# Power_Supply.net
KiCad netlist of a schematic drawn in Altium Designer
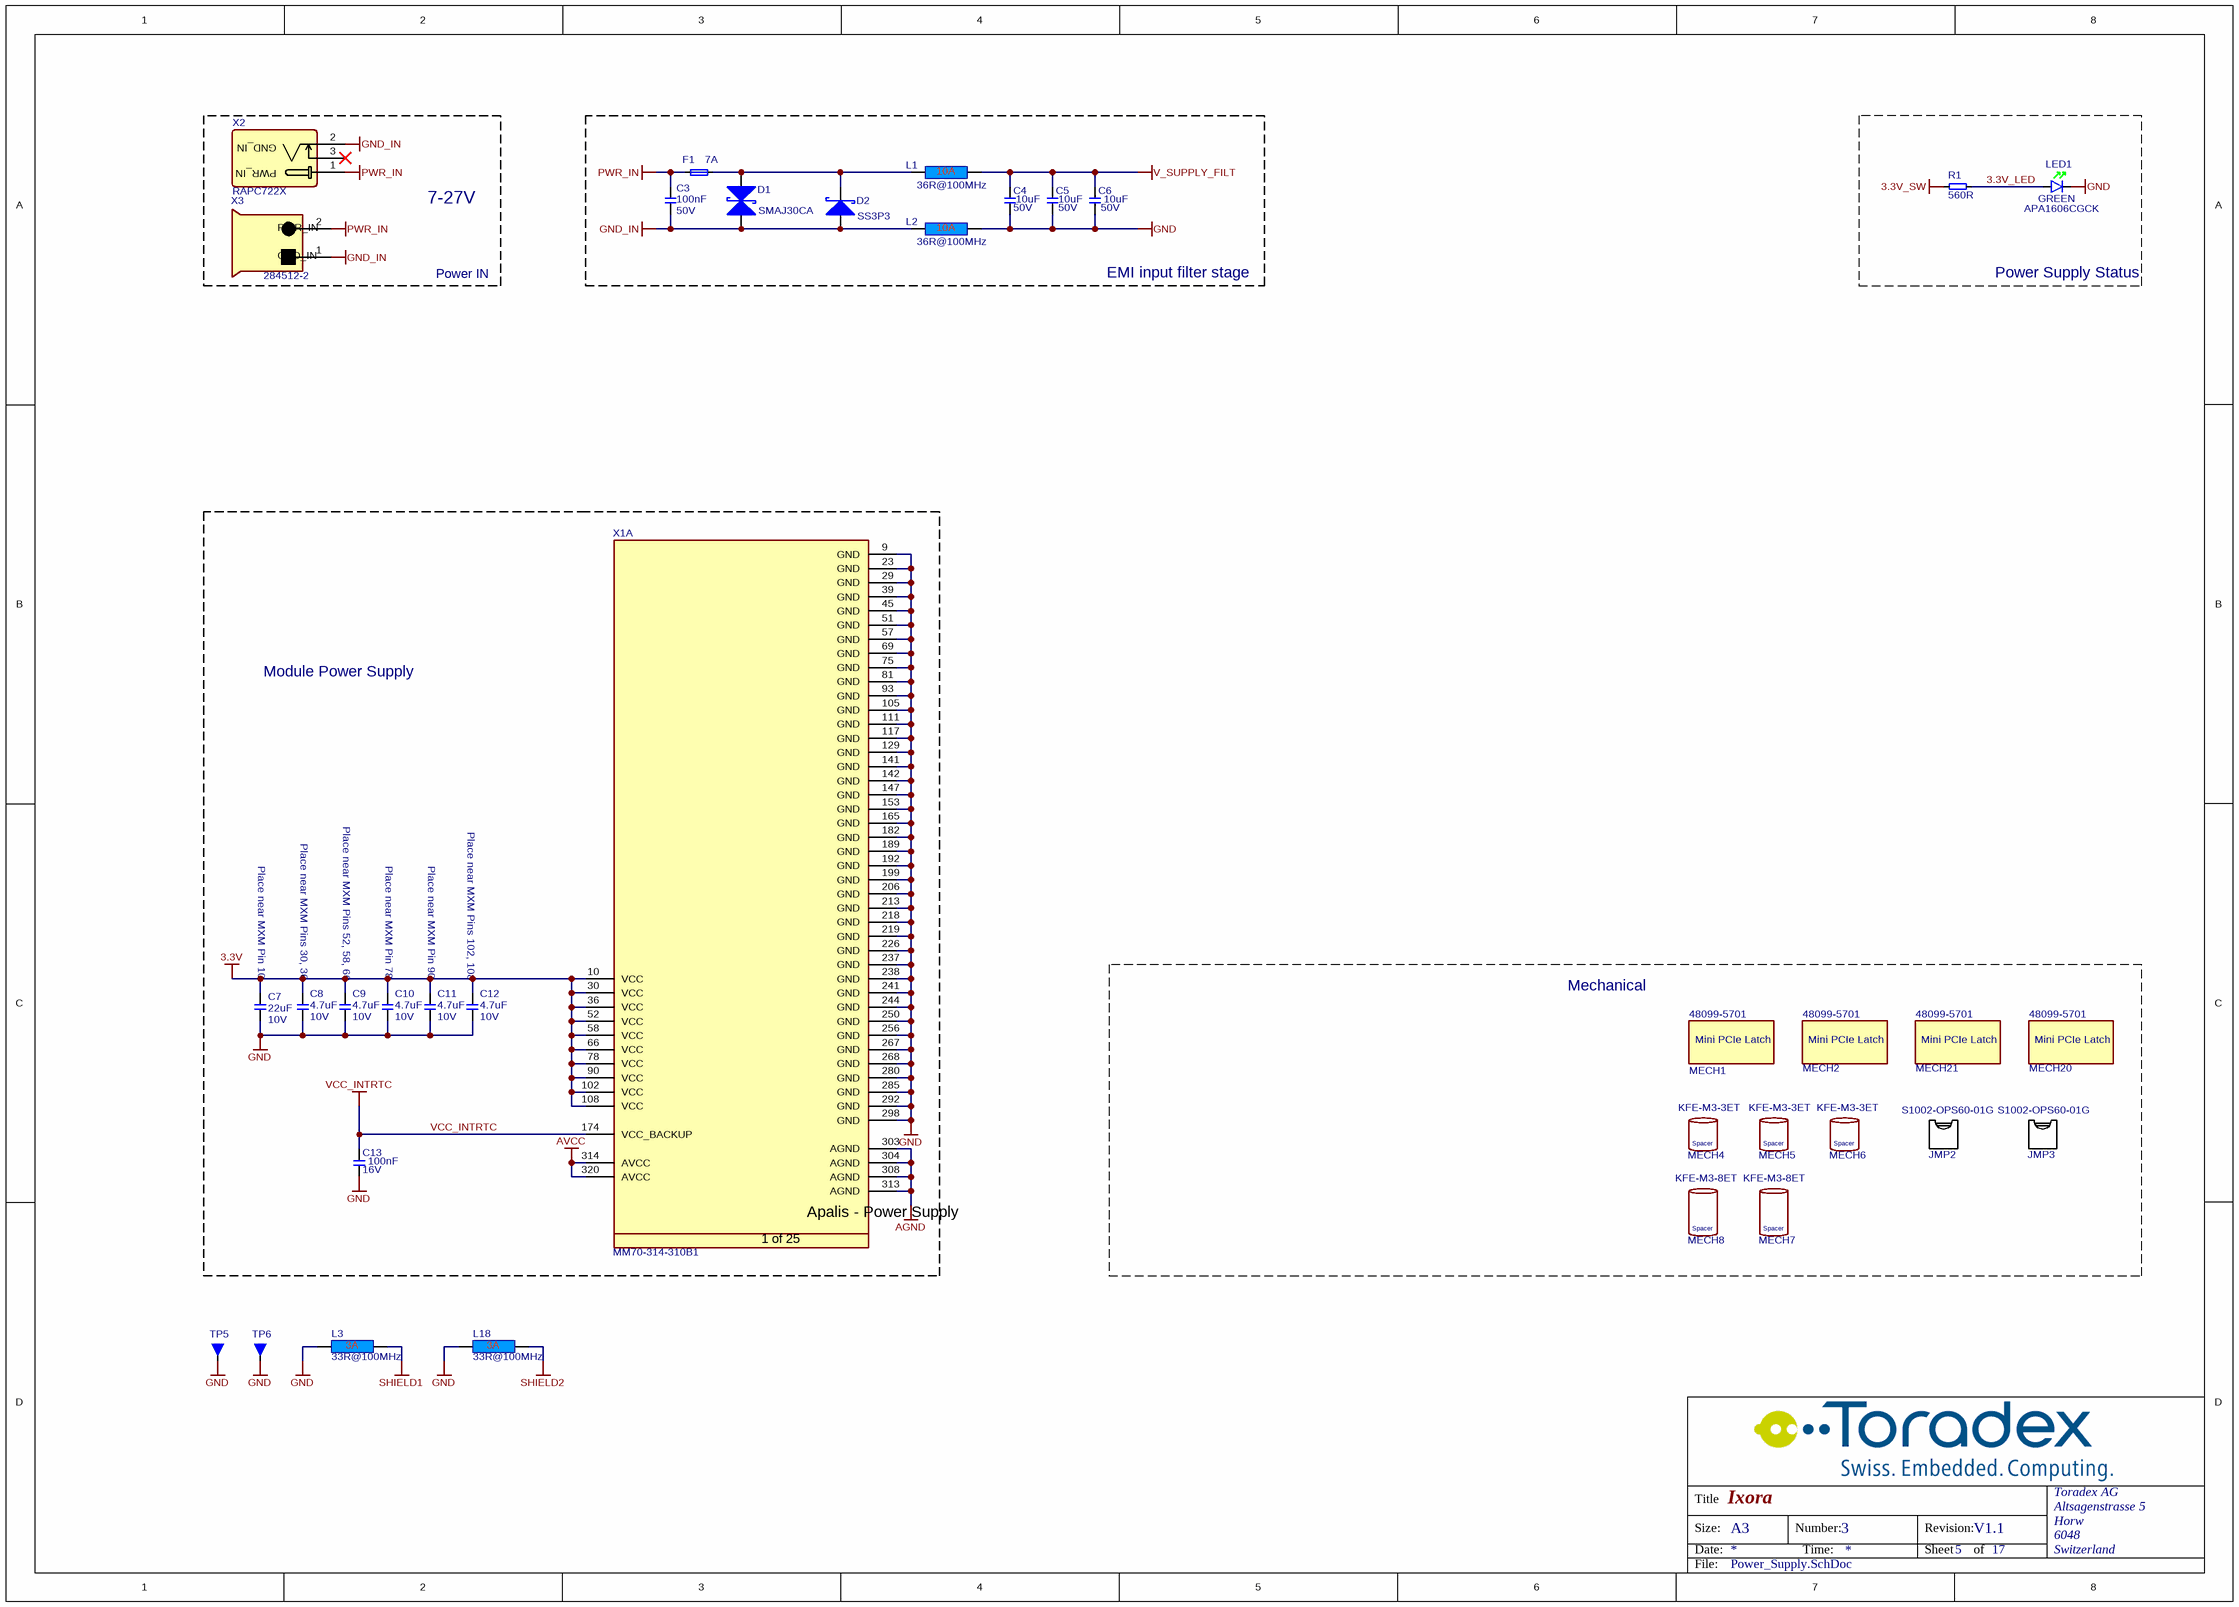
[diagram p0: Power_Supply.SchDoc]

(export (version "E")
  (design (tool "Eeschema 10.0.6"))
  (components
    (comp (ref "C3")
      (value "100nF")
      (footprint "T_CAPC0603X33N")
      (description "Capacitor Ceramic X7R 100nF 50V 20% 0603")
      (fields (field (name "TOLERANCE") "20%") (field (name "RATING") "50V"))
      (libsource (lib "Ixora") (part "C-X7R-100nF-50V-20%-0603"))
    )
    (comp (ref "C4")
      (value "10uF")
      (footprint "CAPC3225X160N")
      (description "Capacitor Ceramic X5R 10uF 50V 20% 1210")
      (fields (field (name "TOLERANCE") "20%") (field (name "RATING") "50V"))
      (libsource (lib "Ixora") (part "C-X5R-10uF-50V-20%-1210"))
    )
    (comp (ref "C5")
      (value "10uF")
      (footprint "CAPC3225X160N")
      (description "Capacitor Ceramic X5R 10uF 50V 20% 1210")
      (fields (field (name "TOLERANCE") "20%") (field (name "RATING") "50V"))
      (libsource (lib "Ixora") (part "C-X5R-10uF-50V-20%-1210"))
    )
    (comp (ref "C6")
      (value "10uF")
      (footprint "CAPC3225X160N")
      (description "Capacitor Ceramic X5R 10uF 50V 20% 1210")
      (fields (field (name "TOLERANCE") "20%") (field (name "RATING") "50V"))
      (libsource (lib "Ixora") (part "C-X5R-10uF-50V-20%-1210"))
    )
    (comp (ref "C7")
      (value "22uF")
      (footprint "T_CAPC0805X125N")
      (description "Capacitor Ceramic X5R 22uF 10V 20% 0805")
      (fields (field (name "TOLERANCE") "20%") (field (name "RATING") "10V"))
      (libsource (lib "Ixora") (part "C-X5R-22uF-10V-20%-0805"))
    )
    (comp (ref "C8")
      (value "4.7uF")
      (footprint "T_CAPC0603X33N")
      (description "Capacitor Ceramic X5R 4.7uF 10V 10% 0603")
      (fields (field (name "TOLERANCE") "10%") (field (name "RATING") "10V"))
      (libsource (lib "Ixora") (part "C-X5R-4.7uF-10V-10%-0603"))
    )
    (comp (ref "C9")
      (value "4.7uF")
      (footprint "T_CAPC0603X33N")
      (description "Capacitor Ceramic X5R 4.7uF 10V 10% 0603")
      (fields (field (name "TOLERANCE") "10%") (field (name "RATING") "10V"))
      (libsource (lib "Ixora") (part "C-X5R-4.7uF-10V-10%-0603"))
    )
    (comp (ref "C10")
      (value "4.7uF")
      (footprint "T_CAPC0603X33N")
      (description "Capacitor Ceramic X5R 4.7uF 10V 10% 0603")
      (fields (field (name "TOLERANCE") "10%") (field (name "RATING") "10V"))
      (libsource (lib "Ixora") (part "C-X5R-4.7uF-10V-10%-0603"))
    )
    (comp (ref "C11")
      (value "4.7uF")
      (footprint "T_CAPC0603X33N")
      (description "Capacitor Ceramic X5R 4.7uF 10V 10% 0603")
      (fields (field (name "TOLERANCE") "10%") (field (name "RATING") "10V"))
      (libsource (lib "Ixora") (part "C-X5R-4.7uF-10V-10%-0603"))
    )
    (comp (ref "C12")
      (value "4.7uF")
      (footprint "T_CAPC0603X33N")
      (description "Capacitor Ceramic X5R 4.7uF 10V 10% 0603")
      (fields (field (name "TOLERANCE") "10%") (field (name "RATING") "10V"))
      (libsource (lib "Ixora") (part "C-X5R-4.7uF-10V-10%-0603"))
    )
    (comp (ref "C13")
      (value "100nF")
      (footprint "CAPC1005X60N")
      (description "Capacitor Ceramic X7R 100nF 16V 10% 0402")
      (fields (field (name "TOLERANCE") "10%") (field (name "RATING") "16V"))
      (libsource (lib "Ixora") (part "C-X7R-100nF-16V-10%-0402"))
    )
    (comp (ref "D1")
      (value "D-Littelfuse-SMAJ30CA-Schottky")
      (footprint "T_LITTLEFUSE_SMAJ30CA")
      (description "Bidirectional ESD protection")
      (fields (field (name "MANUFACTURER PART NO.") "SMAJ30CA"))
      (libsource (lib "Ixora") (part "D-Littelfuse-SMAJ30CA-Schottky"))
    )
    (comp (ref "D2")
      (value "SS3P3")
      (footprint "T_VISHAY_SS3P3")
      (description "SS3P3-E3/84A Schottky Diode")
      (fields (field (name "MANUFACTURER PART NO.") "SS3P3-E3/84A"))
      (libsource (lib "Ixora") (part "D-Vishay-SS3P3-E3/84A-Schottky"))
    )
    (comp (ref "F1")
      (value "7A")
      (footprint "T_Littelfuse_0458")
      (description "Fuse 7A Fast")
      (fields (field (name "MANUFACTURER PART NO.") "0458007"))
      (libsource (lib "Ixora") (part "F-Littelfuse-0458007"))
    )
    (comp (ref "JMP2")
      (value "Shunt Jumper")
      (fields (field (name "MANUFACTURER PART NO.") "S1002-OPS60-01G"))
      (libsource (lib "Ixora") (part "MECH-Shunt-Jumper-Black-2.54mm"))
    )
    (comp (ref "JMP3")
      (value "Shunt Jumper")
      (fields (field (name "MANUFACTURER PART NO.") "S1002-OPS60-01G"))
      (libsource (lib "Ixora") (part "MECH-Shunt-Jumper-Black-2.54mm"))
    )
    (comp (ref "L1")
      (value "36R@100MHz")
      (footprint "T_Laird_35F0121-0SR-10")
      (description "Power Supply FB 10A")
      (fields (field (name "TOLERANCE") "25%"))
      (libsource (lib "Ixora") (part "L-Laird-35F0121-0SR-10-10A-25%"))
    )
    (comp (ref "L2")
      (value "36R@100MHz")
      (footprint "T_Laird_35F0121-0SR-10")
      (description "Power Supply FB 10A")
      (fields (field (name "TOLERANCE") "25%"))
      (libsource (lib "Ixora") (part "L-Laird-35F0121-0SR-10-10A-25%"))
    )
    (comp (ref "L3")
      (value "33R@100MHz")
      (footprint "INDC1608X95N")
      (description "33R@100MHz 3A EMI FILTER")
      (fields (field (name "TOLERANCE") "25%"))
      (libsource (lib "Ixora") (part "L-33R@100MHz-3A-25%-0603"))
    )
    (comp (ref "L18")
      (value "33R@100MHz")
      (footprint "INDC1608X95N")
      (description "33R@100MHz 3A EMI FILTER")
      (fields (field (name "TOLERANCE") "25%"))
      (libsource (lib "Ixora") (part "L-33R@100MHz-3A-25%-0603"))
    )
    (comp (ref "LED1")
      (value "APA1606CGCK")
      (footprint "T_Kingbright_APA1606CGCK")
      (description "LED green Kingbright APA1606CGCK")
      (fields (field (name "COLOR") "GREEN") (field (name "MANUFACTURER PART NO.") "APA1606CGCK"))
      (libsource (lib "Ixora") (part "LED-Kingbright-APA1606CGCK"))
    )
    (comp (ref "MECH1")
      (value "MECH-Mini-PCIe Latch")
      (footprint "T_Molex_48099-5701")
      (description "Mini-PCIe Latch")
      (fields (field (name "MANUFACTURER PART NO.") "48099-5701"))
      (libsource (lib "Ixora") (part "MECH-Molex-48099-5701"))
    )
    (comp (ref "MECH2")
      (value "MECH-Mini-PCIe Latch")
      (footprint "T_Molex_48099-5701")
      (description "Mini-PCIe Latch")
      (fields (field (name "MANUFACTURER PART NO.") "48099-5701"))
      (libsource (lib "Ixora") (part "MECH-Molex-48099-5701"))
    )
    (comp (ref "MECH4")
      (value "KFE-M3-3ET")
      (description "Spacer 3mm M3")
      (fields (field (name "MANUFACTURER PART NO.") "KFE-M3-3ET"))
      (libsource (lib "Ixora") (part "MECH-HiTech-KFE-M3-3ET"))
    )
    (comp (ref "MECH5")
      (value "KFE-M3-3ET")
      (description "Spacer 3mm M3")
      (fields (field (name "MANUFACTURER PART NO.") "KFE-M3-3ET"))
      (libsource (lib "Ixora") (part "MECH-HiTech-KFE-M3-3ET"))
    )
    (comp (ref "MECH6")
      (value "KFE-M3-3ET")
      (description "Spacer 3mm M3")
      (fields (field (name "MANUFACTURER PART NO.") "KFE-M3-3ET"))
      (libsource (lib "Ixora") (part "MECH-HiTech-KFE-M3-3ET"))
    )
    (comp (ref "MECH7")
      (value "KFE-M3-8ET")
      (description "Spacer 8mm M3")
      (fields (field (name "MANUFACTURER PART NO.") "KFE-M3-8ET"))
      (libsource (lib "Ixora") (part "MECH-HiTech-KFE-M3-8ET"))
    )
    (comp (ref "MECH8")
      (value "KFE-M3-8ET")
      (description "Spacer 8mm M3")
      (fields (field (name "MANUFACTURER PART NO.") "KFE-M3-8ET"))
      (libsource (lib "Ixora") (part "MECH-HiTech-KFE-M3-8ET"))
    )
    (comp (ref "MECH20")
      (value "MECH-Mini-PCIe Latch")
      (description "Mini-PCIe Latch")
      (fields (field (name "MANUFACTURER PART NO.") "48099-5701"))
      (libsource (lib "Ixora") (part "MECH-Molex-48099-5701"))
    )
    (comp (ref "MECH21")
      (value "MECH-Mini-PCIe Latch")
      (description "Mini-PCIe Latch")
      (fields (field (name "MANUFACTURER PART NO.") "48099-5701"))
      (libsource (lib "Ixora") (part "MECH-Molex-48099-5701"))
    )
    (comp (ref "R1")
      (value "560R")
      (footprint "RESC1005X40N")
      (description "Resistor 560 ohm 63mW 5% 0402")
      (fields (field (name "TOLERANCE") "5%"))
      (libsource (lib "Ixora") (part "R-560R-63mW-5%-0402"))
    )
    (comp (ref "TP5")
      (value "5011")
      (footprint "T_TP-THT - EYE")
      (description "Testpin Eye TH")
      (libsource (lib "Ixora") (part "TP-Keystone-5011"))
    )
    (comp (ref "TP6")
      (value "5011")
      (footprint "T_TP-THT - EYE")
      (description "Testpin Eye TH")
      (libsource (lib "Ixora") (part "TP-Keystone-5011"))
    )
    (comp (ref "X1")
      (value "CON-JAE-MM70-314-310B1-314-0.5mm")
      (footprint "T_JAE_MM70-314-310B1")
      (description "MXM3 Connector")
      (fields (field (name "MANUFACTURER PART NO.") "MM70-314-310B1"))
      (libsource (lib "Ixora") (part "CON-JAE-MM70-314-310B1-314-0.5mm"))
    )
    (comp (ref "X2")
      (value "RAPC722X")
      (footprint "T_RAPC722X")
      (description "Power Jack")
      (fields (field (name "MANUFACTURER PART NO.") "RAPC722X"))
      (libsource (lib "Ixora") (part "CON-SWC-RAPC722X"))
    )
    (comp (ref "X3")
      (value "284512-2")
      (footprint "T_TYCO_284512-2")
      (description "Power Connector")
      (fields (field (name "MANUFACTURER PART NO.") "284512-2"))
      (libsource (lib "Ixora") (part "CON-Tyco-284512-2-1x2-3.5mm"))
    )
  )
  (nets
    (net (code "1") (name "/3.3V_LED") (class "Default")
      (node (ref "LED1") (pin "2") (pinfunction "A_2") (pintype "passive"))
      (node (ref "R1") (pin "2") (pinfunction "2_2") (pintype "passive"))
    )
    (net (code "2") (name "3.3V") (class "Default")
      (node (ref "C10") (pin "1") (pinfunction "1_1") (pintype "passive"))
      (node (ref "C11") (pin "1") (pinfunction "1_1") (pintype "passive"))
      (node (ref "C12") (pin "1") (pinfunction "1_1") (pintype "passive"))
      (node (ref "C7") (pin "1") (pinfunction "1_1") (pintype "passive"))
      (node (ref "C8") (pin "1") (pinfunction "1_1") (pintype "passive"))
      (node (ref "C9") (pin "1") (pinfunction "1_1") (pintype "passive"))
      (node (ref "X1") (pin "10") (pinfunction "VCC_10") (pintype "passive"))
      (node (ref "X1") (pin "102") (pinfunction "VCC_102") (pintype "passive"))
      (node (ref "X1") (pin "108") (pinfunction "VCC_108") (pintype "passive"))
      (node (ref "X1") (pin "30") (pinfunction "VCC_30") (pintype "passive"))
      (node (ref "X1") (pin "36") (pinfunction "VCC_36") (pintype "passive"))
      (node (ref "X1") (pin "52") (pinfunction "VCC_52") (pintype "passive"))
      (node (ref "X1") (pin "58") (pinfunction "VCC_58") (pintype "passive"))
      (node (ref "X1") (pin "66") (pinfunction "VCC_66") (pintype "passive"))
      (node (ref "X1") (pin "78") (pinfunction "VCC_78") (pintype "passive"))
      (node (ref "X1") (pin "90") (pinfunction "VCC_90") (pintype "passive"))
    )
    (net (code "3") (name "3.3V_SW") (class "Default")
      (node (ref "R1") (pin "1") (pinfunction "1_1") (pintype "passive"))
    )
    (net (code "4") (name "AGND") (class "Default")
      (node (ref "X1") (pin "303") (pinfunction "AGND_303") (pintype "power_in"))
      (node (ref "X1") (pin "304") (pinfunction "AGND_304") (pintype "power_in"))
      (node (ref "X1") (pin "308") (pinfunction "AGND_308") (pintype "power_in"))
      (node (ref "X1") (pin "313") (pinfunction "AGND_313") (pintype "passive"))
    )
    (net (code "5") (name "AVCC") (class "Default")
      (node (ref "X1") (pin "314") (pinfunction "AVCC_314") (pintype "power_in"))
      (node (ref "X1") (pin "320") (pinfunction "AVCC_320") (pintype "passive"))
    )
    (net (code "6") (name "GND") (class "Default")
      (node (ref "C10") (pin "2") (pinfunction "2_2") (pintype "passive"))
      (node (ref "C11") (pin "2") (pinfunction "2_2") (pintype "passive"))
      (node (ref "C12") (pin "2") (pinfunction "2_2") (pintype "passive"))
      (node (ref "C13") (pin "1") (pinfunction "1_1") (pintype "passive"))
      (node (ref "C4") (pin "1") (pinfunction "1_1") (pintype "passive"))
      (node (ref "C5") (pin "1") (pinfunction "1_1") (pintype "passive"))
      (node (ref "C6") (pin "1") (pinfunction "1_1") (pintype "passive"))
      (node (ref "C7") (pin "2") (pinfunction "2_2") (pintype "passive"))
      (node (ref "C8") (pin "2") (pinfunction "2_2") (pintype "passive"))
      (node (ref "C9") (pin "2") (pinfunction "2_2") (pintype "passive"))
      (node (ref "L18") (pin "1") (pinfunction "1_1") (pintype "passive"))
      (node (ref "L2") (pin "2") (pinfunction "2_2") (pintype "passive"))
      (node (ref "L3") (pin "1") (pinfunction "1_1") (pintype "passive"))
      (node (ref "LED1") (pin "1") (pinfunction "K_1") (pintype "passive"))
      (node (ref "TP5") (pin "1") (pinfunction "1_1") (pintype "passive"))
      (node (ref "TP6") (pin "1") (pinfunction "1_1") (pintype "passive"))
      (node (ref "X1") (pin "105") (pinfunction "GND_105") (pintype "power_in"))
      (node (ref "X1") (pin "111") (pinfunction "GND_111") (pintype "power_in"))
      (node (ref "X1") (pin "117") (pinfunction "GND_117") (pintype "power_in"))
      (node (ref "X1") (pin "129") (pinfunction "GND_129") (pintype "power_in"))
      (node (ref "X1") (pin "141") (pinfunction "GND_141") (pintype "power_in"))
      (node (ref "X1") (pin "142") (pinfunction "GND_142") (pintype "power_in"))
      (node (ref "X1") (pin "147") (pinfunction "GND_147") (pintype "power_in"))
      (node (ref "X1") (pin "153") (pinfunction "GND_153") (pintype "power_in"))
      (node (ref "X1") (pin "165") (pinfunction "GND_165") (pintype "power_in"))
      (node (ref "X1") (pin "182") (pinfunction "GND_182") (pintype "power_in"))
      (node (ref "X1") (pin "189") (pinfunction "GND_189") (pintype "power_in"))
      (node (ref "X1") (pin "192") (pinfunction "GND_192") (pintype "power_in"))
      (node (ref "X1") (pin "199") (pinfunction "GND_199") (pintype "power_in"))
      (node (ref "X1") (pin "206") (pinfunction "GND_206") (pintype "power_in"))
      (node (ref "X1") (pin "213") (pinfunction "GND_213") (pintype "power_in"))
      (node (ref "X1") (pin "218") (pinfunction "GND_218") (pintype "power_in"))
      (node (ref "X1") (pin "219") (pinfunction "GND_219") (pintype "power_in"))
      (node (ref "X1") (pin "226") (pinfunction "GND_226") (pintype "power_in"))
      (node (ref "X1") (pin "23") (pinfunction "GND_23") (pintype "passive"))
      (node (ref "X1") (pin "237") (pinfunction "GND_237") (pintype "power_in"))
      (node (ref "X1") (pin "238") (pinfunction "GND_238") (pintype "power_in"))
      (node (ref "X1") (pin "241") (pinfunction "GND_241") (pintype "power_in"))
      (node (ref "X1") (pin "244") (pinfunction "GND_244") (pintype "power_in"))
      (node (ref "X1") (pin "250") (pinfunction "GND_250") (pintype "power_in"))
      (node (ref "X1") (pin "256") (pinfunction "GND_256") (pintype "power_in"))
      (node (ref "X1") (pin "267") (pinfunction "GND_267") (pintype "power_in"))
      (node (ref "X1") (pin "268") (pinfunction "GND_268") (pintype "power_in"))
      (node (ref "X1") (pin "280") (pinfunction "GND_280") (pintype "power_in"))
      (node (ref "X1") (pin "285") (pinfunction "GND_285") (pintype "power_in"))
      (node (ref "X1") (pin "29") (pinfunction "GND_29") (pintype "power_in"))
      (node (ref "X1") (pin "292") (pinfunction "GND_292") (pintype "power_in"))
      (node (ref "X1") (pin "298") (pinfunction "GND_298") (pintype "power_in"))
      (node (ref "X1") (pin "39") (pinfunction "GND_39") (pintype "power_in"))
      (node (ref "X1") (pin "45") (pinfunction "GND_45") (pintype "power_in"))
      (node (ref "X1") (pin "51") (pinfunction "GND_51") (pintype "power_in"))
      (node (ref "X1") (pin "57") (pinfunction "GND_57") (pintype "power_in"))
      (node (ref "X1") (pin "69") (pinfunction "GND_69") (pintype "power_in"))
      (node (ref "X1") (pin "75") (pinfunction "GND_75") (pintype "power_in"))
      (node (ref "X1") (pin "81") (pinfunction "GND_81") (pintype "power_in"))
      (node (ref "X1") (pin "9") (pinfunction "GND_9") (pintype "passive"))
      (node (ref "X1") (pin "93") (pinfunction "GND_93") (pintype "power_in"))
    )
    (net (code "7") (name "GND_IN") (class "Default")
      (node (ref "C3") (pin "1") (pinfunction "1_1") (pintype "passive"))
      (node (ref "D1") (pin "2") (pinfunction "Anode_2") (pintype "passive"))
      (node (ref "D2") (pin "2") (pinfunction "2_2") (pintype "passive"))
      (node (ref "L2") (pin "1") (pinfunction "1_1") (pintype "passive"))
      (node (ref "X2") (pin "2") (pinfunction "PWR_IN_2") (pintype "passive"))
      (node (ref "X3") (pin "1") (pinfunction "GND_IN_1") (pintype "passive"))
    )
    (net (code "8") (name "Net-(D1-Cathode)") (class "Default")
      (node (ref "D1") (pin "1") (pinfunction "Cathode_1") (pintype "passive"))
      (node (ref "D2") (pin "1") (pinfunction "1_1") (pintype "passive"))
      (node (ref "F1") (pin "2") (pinfunction "2_2") (pintype "passive"))
      (node (ref "L1") (pin "1") (pinfunction "1_1") (pintype "passive"))
    )
    (net (code "9") (name "PWR_IN") (class "Default")
      (node (ref "C3") (pin "2") (pinfunction "2_2") (pintype "passive"))
      (node (ref "F1") (pin "1") (pinfunction "1_1") (pintype "passive"))
      (node (ref "X2") (pin "1") (pinfunction "GND_IN_1") (pintype "passive"))
      (node (ref "X3") (pin "2") (pinfunction "PWR_IN_2") (pintype "passive"))
    )
    (net (code "10") (name "SHIELD1") (class "Default")
      (node (ref "L3") (pin "2") (pinfunction "2_2") (pintype "passive"))
    )
    (net (code "11") (name "SHIELD2") (class "Default")
      (node (ref "L18") (pin "2") (pinfunction "2_2") (pintype "passive"))
    )
    (net (code "12") (name "VCC_INTRTC") (class "Default")
      (node (ref "C13") (pin "2") (pinfunction "2_2") (pintype "passive"))
      (node (ref "X1") (pin "174") (pinfunction "VCC_BACKUP_174") (pintype "passive"))
    )
    (net (code "13") (name "V_SUPPLY_FILT") (class "Default")
      (node (ref "C4") (pin "2") (pinfunction "2_2") (pintype "passive"))
      (node (ref "C5") (pin "2") (pinfunction "2_2") (pintype "passive"))
      (node (ref "C6") (pin "2") (pinfunction "2_2") (pintype "passive"))
      (node (ref "L1") (pin "2") (pinfunction "2_2") (pintype "passive"))
    )
    (net (code "14") (name "unconnected-(X2-PWR_IN-Pad3)") (class "Default")
      (node (ref "X2") (pin "3") (pinfunction "PWR_IN_3") (pintype "passive+no_connect"))
    )
  )
)
